# IRGenerator.net
KiCad netlist of a schematic drawn in Altium Designer
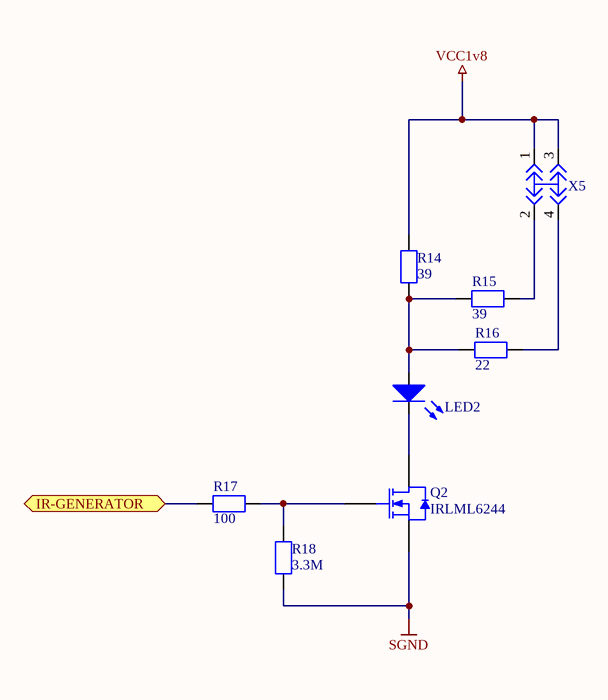
[diagram p0: IRGenerator.SchDoc]

(export (version "E")
  (design (tool "Eeschema 10.0.6"))
  (components
    (comp (ref "LED2")
      (value "L53F3C")
      (footprint "LED-5-SHORT-LEGS")
      (description "IR LED")
      (libsource (lib "MCounter_Common") (part "L53F3C"))
    )
    (comp (ref "Q2")
      (value "IRLML6244")
      (footprint "SOT23_N")
      (description "N-Channel Power MOSFET")
      (libsource (lib "MCounter_Common") (part "IRLML6244"))
    )
    (comp (ref "R14")
      (value "39")
      (footprint "R1206")
      (description "R39-5%")
      (libsource (lib "") (part "R39-5%_1"))
    )
    (comp (ref "R15")
      (value "39")
      (footprint "R1206")
      (description "R39-5%")
      (libsource (lib "MCounter_Common") (part "R39-5%"))
    )
    (comp (ref "R16")
      (value "22")
      (footprint "R0805")
      (description "R22-5%")
      (libsource (lib "MCounter_Common") (part "R22-5%"))
    )
    (comp (ref "R17")
      (value "100")
      (footprint "R0805")
      (description "R-100-5%")
      (fields (field (name "Comment") "R100-5%"))
      (libsource (lib "MCounter_Common") (part "R100-5%"))
    )
    (comp (ref "R18")
      (value "3.3M")
      (footprint "R0805")
      (description "R3.3M-5%")
      (libsource (lib "MCounter_Common") (part "R3.3M-5%"))
    )
    (comp (ref "X5")
      (value "JUMPER-PLD-POWER-0-1-2")
      (footprint "PLD-POWER-0-1-2")
      (libsource (lib "MCounter_Common") (part "JUMPER-PLD-POWER-0-1-2"))
    )
  )
  (nets
    (net (code "1") (name "/IR-GENERATOR") (class "Default")
      (node (ref "R17") (pin "1") (pinfunction "1_1") (pintype "passive"))
    )
    (net (code "2") (name "Net-(LED2-A)") (class "Default")
      (node (ref "LED2") (pin "1") (pinfunction "A_1") (pintype "passive"))
      (node (ref "R14") (pin "1") (pinfunction "1_1") (pintype "passive"))
      (node (ref "R15") (pin "2") (pinfunction "2_2") (pintype "passive"))
      (node (ref "R16") (pin "1") (pinfunction "1_1") (pintype "passive"))
    )
    (net (code "3") (name "Net-(LED2-K)") (class "Default")
      (node (ref "LED2") (pin "2") (pinfunction "K_2") (pintype "passive"))
      (node (ref "Q2") (pin "3") (pinfunction "D_3") (pintype "passive"))
    )
    (net (code "4") (name "Net-(Q2-G)") (class "Default")
      (node (ref "Q2") (pin "1") (pinfunction "G_1") (pintype "passive"))
      (node (ref "R17") (pin "2") (pinfunction "2_2") (pintype "passive"))
      (node (ref "R18") (pin "1") (pinfunction "1_1") (pintype "passive"))
    )
    (net (code "5") (name "Net-(R15-Pad1)") (class "Default")
      (node (ref "R15") (pin "1") (pinfunction "1_1") (pintype "passive"))
      (node (ref "X5") (pin "2") (pinfunction "2_2") (pintype "passive"))
    )
    (net (code "6") (name "Net-(R16-Pad2)") (class "Default")
      (node (ref "R16") (pin "2") (pinfunction "2_2") (pintype "passive"))
      (node (ref "X5") (pin "4") (pinfunction "4_4") (pintype "passive"))
    )
    (net (code "7") (name "SGND") (class "Default")
      (node (ref "Q2") (pin "2") (pinfunction "S_2") (pintype "passive"))
      (node (ref "R18") (pin "2") (pinfunction "2_2") (pintype "passive"))
    )
    (net (code "8") (name "VCC1v8") (class "Default")
      (node (ref "R14") (pin "2") (pinfunction "2_2") (pintype "passive"))
      (node (ref "X5") (pin "1") (pinfunction "1_1") (pintype "passive"))
      (node (ref "X5") (pin "3") (pinfunction "3_3") (pintype "passive"))
    )
  )
)
